# 5V_Enable.net
KiCad netlist of a schematic drawn in Altium Designer
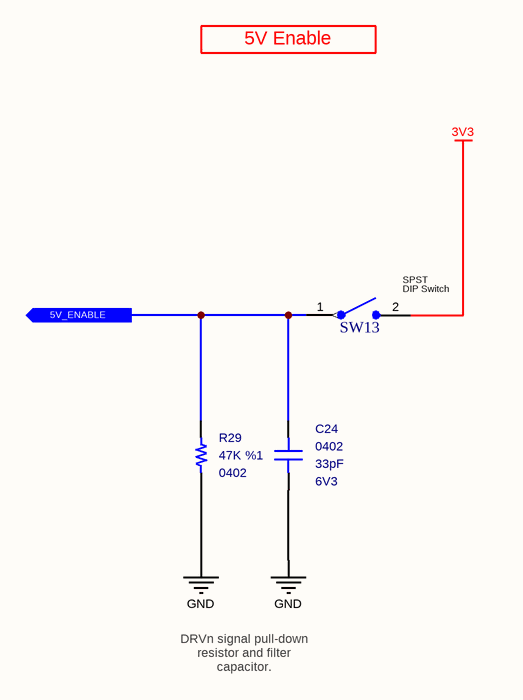
[diagram p0: 5V Enable.SchDoc]

(export (version "E")
  (design (tool "Eeschema 10.0.6"))
  (components
    (comp (ref "C24")
      (value "33pF")
      (footprint "CAPACITOR_0402")
      (description "Capacitor - 33pF [0402] (Ceramic)")
      (fields
        (field (name "MANUFACTURER_PART_NUMBER") "C0402C330J9RACAUTO")
        (field (name "MOUSER_PART_NUMBER") "80-C0402C330J9RAUTO")
        (field (name "CASE") "0402")
        (field (name "VOLTAGE") "6V3")
      )
      (libsource (lib "Ovoo_Schematic") (part "Capacitor - 33pF [0402-6V3]"))
    )
    (comp (ref "R29")
      (value "47K")
      (footprint "RESISTOR_0402")
      (description "Thick Film Resistors - SMD 1/16 W 47 Kohms 1%")
      (fields
        (field (name "MANUFACTURER_PART_NUMBER") "CRCW040247K0FKED")
        (field (name "MOUSER_PART_NUMBER") "71-CRCW0402-47K-E3")
        (field (name "TOLERANCE") "%1")
        (field (name "CASE") "0402")
      )
      (libsource (lib "Ovoo_Schematic") (part "Resistor - 47K"))
    )
    (comp (ref "SW13")
      (value "DIP Switch")
      (footprint "DS04-254-2-01BK-SMT-TR")
      (fields
        (field (name "MANUFACTURER PART NUMBER") "DS04-254-2-01BK-SMT-TR")
        (field (name "MOUSER PART NUMBER") "490-DS04254201BK-STR")
      )
      (libsource (lib "Ovoo_Library") (part "Switch - DIP Switch (1 Pole)"))
    )
  )
  (nets
    (net (code "1") (name "/5V_ENABLE") (class "Default")
      (node (ref "C24") (pin "2") (pinfunction "2_2") (pintype "passive"))
      (node (ref "R29") (pin "2") (pinfunction "2_2") (pintype "passive"))
      (node (ref "SW13") (pin "1") (pinfunction "COM_1") (pintype "output"))
    )
    (net (code "2") (name "3V3") (class "Default")
      (node (ref "SW13") (pin "2") (pinfunction "NO_2") (pintype "passive"))
    )
    (net (code "3") (name "GND") (class "Default")
      (node (ref "C24") (pin "1") (pinfunction "1_1") (pintype "passive"))
      (node (ref "R29") (pin "1") (pinfunction "1_1") (pintype "passive"))
    )
  )
)
